# Sheet1.net
KiCad netlist of a schematic drawn in Altium Designer
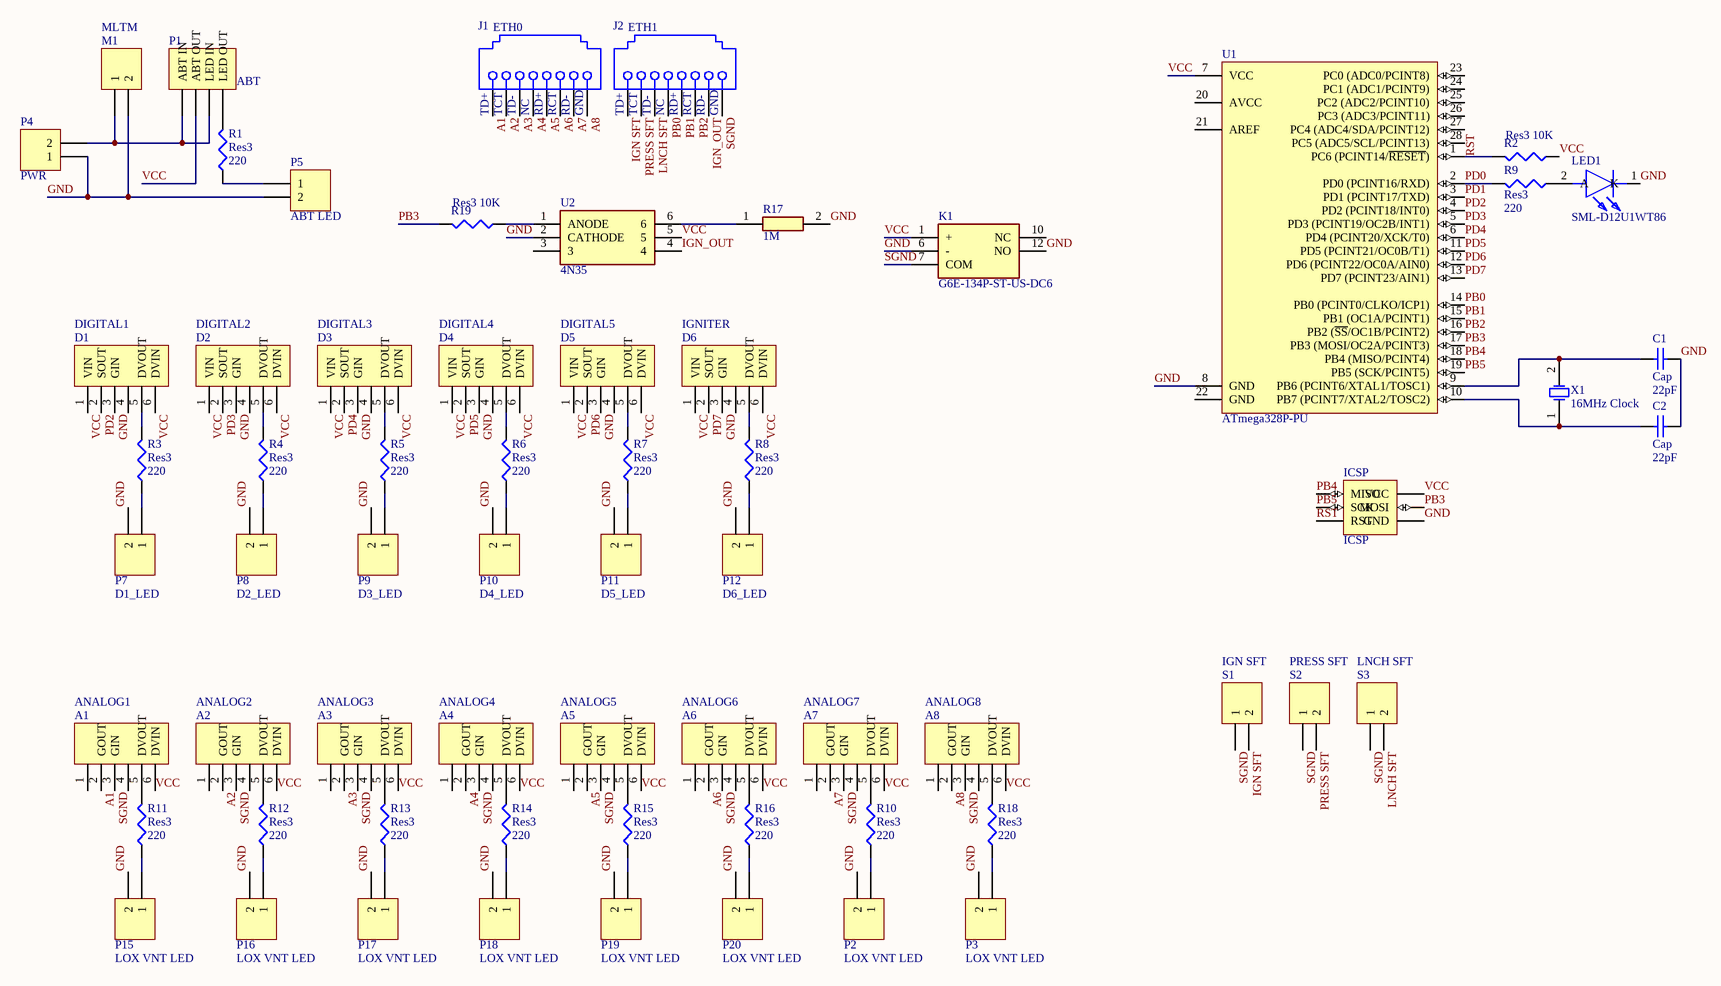
[diagram p0: Sheet1.SchDoc]

(export (version "E")
  (design (tool "Eeschema 10.0.6"))
  (components
    (comp (ref "A1")
      (value "ANALOG1")
      (footprint "HDR1X6")
      (description "Header, 6-Pin")
      (fields (field (name "PUBLISHER") "Altium Limited"))
      (libsource (lib "Miscellaneous Connectors") (part "Header 6"))
    )
    (comp (ref "A2")
      (value "ANALOG2")
      (footprint "HDR1X6")
      (description "Header, 6-Pin")
      (fields (field (name "PUBLISHER") "Altium Limited"))
      (libsource (lib "Miscellaneous Connectors") (part "Header 6"))
    )
    (comp (ref "A3")
      (value "ANALOG3")
      (footprint "HDR1X6")
      (description "Header, 6-Pin")
      (fields (field (name "PUBLISHER") "Altium Limited"))
      (libsource (lib "Miscellaneous Connectors") (part "Header 6"))
    )
    (comp (ref "A4")
      (value "ANALOG4")
      (footprint "HDR1X6")
      (description "Header, 6-Pin")
      (fields (field (name "PUBLISHER") "Altium Limited"))
      (libsource (lib "Miscellaneous Connectors") (part "Header 6"))
    )
    (comp (ref "A5")
      (value "ANALOG5")
      (footprint "HDR1X6")
      (description "Header, 6-Pin")
      (fields (field (name "PUBLISHER") "Altium Limited"))
      (libsource (lib "Miscellaneous Connectors") (part "Header 6"))
    )
    (comp (ref "A6")
      (value "ANALOG6")
      (footprint "HDR1X6")
      (description "Header, 6-Pin")
      (fields (field (name "PUBLISHER") "Altium Limited"))
      (libsource (lib "Miscellaneous Connectors") (part "Header 6"))
    )
    (comp (ref "A7")
      (value "ANALOG7")
      (footprint "HDR1X6")
      (description "Header, 6-Pin")
      (fields (field (name "PUBLISHER") "Altium Limited"))
      (libsource (lib "Miscellaneous Connectors") (part "Header 6"))
    )
    (comp (ref "A8")
      (value "ANALOG8")
      (footprint "HDR1X6")
      (description "Header, 6-Pin")
      (fields (field (name "PUBLISHER") "Altium Limited"))
      (libsource (lib "Miscellaneous Connectors") (part "Header 6"))
    )
    (comp (ref "C1")
      (value "Cap")
      (footprint "RAD-0.3")
      (description "Capacitor")
      (fields (field (name "ALTIUM_VALUE") "22pF") (field (name "PUBLISHER") "Altium Limited"))
      (libsource (lib "Miscellaneous Devices") (part "Cap"))
    )
    (comp (ref "C2")
      (value "Cap")
      (footprint "RAD-0.3")
      (description "Capacitor")
      (fields (field (name "ALTIUM_VALUE") "22pF") (field (name "PUBLISHER") "Altium Limited"))
      (libsource (lib "Miscellaneous Devices") (part "Cap"))
    )
    (comp (ref "D1")
      (value "DIGITAL1")
      (footprint "HDR1X6")
      (description "Header, 6-Pin")
      (fields (field (name "PUBLISHER") "Altium Limited"))
      (libsource (lib "Miscellaneous Connectors") (part "Header 6"))
    )
    (comp (ref "D2")
      (value "DIGITAL2")
      (footprint "HDR1X6")
      (description "Header, 6-Pin")
      (fields (field (name "PUBLISHER") "Altium Limited"))
      (libsource (lib "Miscellaneous Connectors") (part "Header 6"))
    )
    (comp (ref "D3")
      (value "DIGITAL3")
      (footprint "HDR1X6")
      (description "Header, 6-Pin")
      (fields (field (name "PUBLISHER") "Altium Limited"))
      (libsource (lib "Miscellaneous Connectors") (part "Header 6"))
    )
    (comp (ref "D4")
      (value "DIGITAL4")
      (footprint "HDR1X6")
      (description "Header, 6-Pin")
      (fields (field (name "PUBLISHER") "Altium Limited"))
      (libsource (lib "Miscellaneous Connectors") (part "Header 6"))
    )
    (comp (ref "D5")
      (value "DIGITAL5")
      (footprint "HDR1X6")
      (description "Header, 6-Pin")
      (fields (field (name "PUBLISHER") "Altium Limited"))
      (libsource (lib "Miscellaneous Connectors") (part "Header 6"))
    )
    (comp (ref "D6")
      (value "IGNITER")
      (footprint "HDR1X6")
      (description "Header, 6-Pin")
      (fields (field (name "PUBLISHER") "Altium Limited"))
      (libsource (lib "Miscellaneous Connectors") (part "Header 6"))
    )
    (comp (ref "ICSP")
      (value "ICSP")
      (footprint "HDR2X3")
      (description "Header, 3-Pin, Dual row")
      (fields (field (name "PUBLISHER") "Altium Limited"))
      (libsource (lib "Miscellaneous Connectors") (part "Header 3X2"))
    )
    (comp (ref "J1")
      (value "ETH0")
      (footprint "TECO-5555153-1_V")
      (fields (field (name "MANUFACTURER") "TE Connectivity"))
      (libsource (lib "Altium Content Vault") (part "RJ45-8-2SHLD"))
    )
    (comp (ref "J2")
      (value "ETH1")
      (footprint "TECO-5555153-1_V")
      (fields (field (name "MANUFACTURER") "TE Connectivity"))
      (libsource (lib "Altium Content Vault") (part "RJ45-8-2SHLD"))
    )
    (comp (ref "K1")
      (value "G6E-134P-ST-US-DC6")
      (footprint "SamacSys:G6E-134P-US")
      (description "Relay or Contactor")
      (fields (field (name "MOUSER PART NUMBER") "653-G6E134PSTUSDC6"))
      (libsource (lib "*") (part "G6E-134P-ST-US-DC6"))
    )
    (comp (ref "LED1")
      (value "SML-D12U1WT86")
      (footprint "SamacSys:LEDC1608X65N")
      (description "LED")
      (fields
        (field (name "MOUSER PART NUMBER") "755-SML-D12U1WT86")
        (field (name "RS PART NUMBER") "1332870")
      )
      (libsource (lib "*") (part "SML-D12U1WT86"))
    )
    (comp (ref "M1")
      (value "MLTM")
      (footprint "HDR1X2")
      (description "Header, 2-Pin")
      (fields (field (name "PUBLISHER") "Altium Limited"))
      (libsource (lib "Miscellaneous Connectors") (part "Header 2"))
    )
    (comp (ref "P1")
      (value "ABT")
      (footprint "HDR1X4")
      (description "Header, 4-Pin")
      (fields (field (name "PUBLISHER") "Altium Limited"))
      (libsource (lib "Miscellaneous Connectors") (part "Header 4"))
    )
    (comp (ref "P2")
      (value "LOX VNT LED")
      (footprint "HDR1X2")
      (description "Header, 2-Pin")
      (fields (field (name "PUBLISHER") "Altium Limited"))
      (libsource (lib "") (part "Header 2_1"))
    )
    (comp (ref "P3")
      (value "LOX VNT LED")
      (footprint "HDR1X2")
      (description "Header, 2-Pin")
      (fields (field (name "PUBLISHER") "Altium Limited"))
      (libsource (lib "") (part "Header 2_1"))
    )
    (comp (ref "P4")
      (value "PWR")
      (footprint "HDR1X2")
      (description "Header, 2-Pin")
      (fields (field (name "PUBLISHER") "Altium Limited"))
      (libsource (lib "") (part "Header 2_2"))
    )
    (comp (ref "P5")
      (value "ABT LED")
      (footprint "HDR1X2")
      (description "Header, 2-Pin")
      (fields (field (name "PUBLISHER") "Altium Limited"))
      (libsource (lib "") (part "Header 2_3"))
    )
    (comp (ref "P7")
      (value "D1_LED")
      (footprint "HDR1X2")
      (description "Header, 2-Pin")
      (fields (field (name "PUBLISHER") "Altium Limited"))
      (libsource (lib "") (part "Header 2_1"))
    )
    (comp (ref "P8")
      (value "D2_LED")
      (footprint "HDR1X2")
      (description "Header, 2-Pin")
      (fields (field (name "PUBLISHER") "Altium Limited"))
      (libsource (lib "") (part "Header 2_1"))
    )
    (comp (ref "P9")
      (value "D3_LED")
      (footprint "HDR1X2")
      (description "Header, 2-Pin")
      (fields (field (name "PUBLISHER") "Altium Limited"))
      (libsource (lib "") (part "Header 2_1"))
    )
    (comp (ref "P10")
      (value "D4_LED")
      (footprint "HDR1X2")
      (description "Header, 2-Pin")
      (fields (field (name "PUBLISHER") "Altium Limited"))
      (libsource (lib "") (part "Header 2_1"))
    )
    (comp (ref "P11")
      (value "D5_LED")
      (footprint "HDR1X2")
      (description "Header, 2-Pin")
      (fields (field (name "PUBLISHER") "Altium Limited"))
      (libsource (lib "") (part "Header 2_1"))
    )
    (comp (ref "P12")
      (value "D6_LED")
      (footprint "HDR1X2")
      (description "Header, 2-Pin")
      (fields (field (name "PUBLISHER") "Altium Limited"))
      (libsource (lib "") (part "Header 2_1"))
    )
    (comp (ref "P15")
      (value "LOX VNT LED")
      (footprint "HDR1X2")
      (description "Header, 2-Pin")
      (fields (field (name "PUBLISHER") "Altium Limited"))
      (libsource (lib "") (part "Header 2_1"))
    )
    (comp (ref "P16")
      (value "LOX VNT LED")
      (footprint "HDR1X2")
      (description "Header, 2-Pin")
      (fields (field (name "PUBLISHER") "Altium Limited"))
      (libsource (lib "") (part "Header 2_1"))
    )
    (comp (ref "P17")
      (value "LOX VNT LED")
      (footprint "HDR1X2")
      (description "Header, 2-Pin")
      (fields (field (name "PUBLISHER") "Altium Limited"))
      (libsource (lib "") (part "Header 2_1"))
    )
    (comp (ref "P18")
      (value "LOX VNT LED")
      (footprint "HDR1X2")
      (description "Header, 2-Pin")
      (fields (field (name "PUBLISHER") "Altium Limited"))
      (libsource (lib "") (part "Header 2_1"))
    )
    (comp (ref "P19")
      (value "LOX VNT LED")
      (footprint "HDR1X2")
      (description "Header, 2-Pin")
      (fields (field (name "PUBLISHER") "Altium Limited"))
      (libsource (lib "") (part "Header 2_1"))
    )
    (comp (ref "P20")
      (value "LOX VNT LED")
      (footprint "HDR1X2")
      (description "Header, 2-Pin")
      (fields (field (name "PUBLISHER") "Altium Limited"))
      (libsource (lib "") (part "Header 2_1"))
    )
    (comp (ref "R1")
      (value "Res3")
      (footprint "*RESC3146X60N")
      (description "Resistor")
      (fields (field (name "ALTIUM_VALUE") "220") (field (name "PUBLISHER") "Altium Limited"))
      (libsource (lib "Miscellaneous Devices") (part "Res3"))
    )
    (comp (ref "R2")
      (value "Res3")
      (footprint "*RESC3146X60N")
      (description "Resistor")
      (fields (field (name "ALTIUM_VALUE") "10K") (field (name "PUBLISHER") "Altium Limited"))
      (libsource (lib "Miscellaneous Devices") (part "Res3"))
    )
    (comp (ref "R3")
      (value "Res3")
      (footprint "*RESC3146X60N")
      (description "Resistor")
      (fields (field (name "ALTIUM_VALUE") "220") (field (name "PUBLISHER") "Altium Limited"))
      (libsource (lib "Miscellaneous Devices") (part "Res3"))
    )
    (comp (ref "R4")
      (value "Res3")
      (footprint "*RESC3146X60N")
      (description "Resistor")
      (fields (field (name "ALTIUM_VALUE") "220") (field (name "PUBLISHER") "Altium Limited"))
      (libsource (lib "Miscellaneous Devices") (part "Res3"))
    )
    (comp (ref "R5")
      (value "Res3")
      (footprint "*RESC3146X60N")
      (description "Resistor")
      (fields (field (name "ALTIUM_VALUE") "220") (field (name "PUBLISHER") "Altium Limited"))
      (libsource (lib "Miscellaneous Devices") (part "Res3"))
    )
    (comp (ref "R6")
      (value "Res3")
      (footprint "*RESC3146X60N")
      (description "Resistor")
      (fields (field (name "ALTIUM_VALUE") "220") (field (name "PUBLISHER") "Altium Limited"))
      (libsource (lib "Miscellaneous Devices") (part "Res3"))
    )
    (comp (ref "R7")
      (value "Res3")
      (footprint "*RESC3146X60N")
      (description "Resistor")
      (fields (field (name "ALTIUM_VALUE") "220") (field (name "PUBLISHER") "Altium Limited"))
      (libsource (lib "Miscellaneous Devices") (part "Res3"))
    )
    (comp (ref "R8")
      (value "Res3")
      (footprint "*RESC3146X60N")
      (description "Resistor")
      (fields (field (name "ALTIUM_VALUE") "220") (field (name "PUBLISHER") "Altium Limited"))
      (libsource (lib "Miscellaneous Devices") (part "Res3"))
    )
    (comp (ref "R9")
      (value "Res3")
      (footprint "*RESC3146X60N")
      (description "Resistor")
      (fields (field (name "ALTIUM_VALUE") "220") (field (name "PUBLISHER") "Altium Limited"))
      (libsource (lib "Miscellaneous Devices") (part "Res3"))
    )
    (comp (ref "R10")
      (value "Res3")
      (footprint "*RESC3146X60N")
      (description "Resistor")
      (fields (field (name "ALTIUM_VALUE") "220") (field (name "PUBLISHER") "Altium Limited"))
      (libsource (lib "Miscellaneous Devices") (part "Res3"))
    )
    (comp (ref "R11")
      (value "Res3")
      (footprint "*RESC3146X60N")
      (description "Resistor")
      (fields (field (name "ALTIUM_VALUE") "220") (field (name "PUBLISHER") "Altium Limited"))
      (libsource (lib "Miscellaneous Devices") (part "Res3"))
    )
    (comp (ref "R12")
      (value "Res3")
      (footprint "*RESC3146X60N")
      (description "Resistor")
      (fields (field (name "ALTIUM_VALUE") "220") (field (name "PUBLISHER") "Altium Limited"))
      (libsource (lib "Miscellaneous Devices") (part "Res3"))
    )
    (comp (ref "R13")
      (value "Res3")
      (footprint "*RESC3146X60N")
      (description "Resistor")
      (fields (field (name "ALTIUM_VALUE") "220") (field (name "PUBLISHER") "Altium Limited"))
      (libsource (lib "Miscellaneous Devices") (part "Res3"))
    )
    (comp (ref "R14")
      (value "Res3")
      (footprint "*RESC3146X60N")
      (description "Resistor")
      (fields (field (name "ALTIUM_VALUE") "220") (field (name "PUBLISHER") "Altium Limited"))
      (libsource (lib "Miscellaneous Devices") (part "Res3"))
    )
    (comp (ref "R15")
      (value "Res3")
      (footprint "*RESC3146X60N")
      (description "Resistor")
      (fields (field (name "ALTIUM_VALUE") "220") (field (name "PUBLISHER") "Altium Limited"))
      (libsource (lib "Miscellaneous Devices") (part "Res3"))
    )
    (comp (ref "R16")
      (value "Res3")
      (footprint "*RESC3146X60N")
      (description "Resistor")
      (fields (field (name "ALTIUM_VALUE") "220") (field (name "PUBLISHER") "Altium Limited"))
      (libsource (lib "Miscellaneous Devices") (part "Res3"))
    )
    (comp (ref "R17")
      (value "1M")
      (footprint "SamacSys:RESAD1550W60L630D230")
      (description "Resistor")
      (fields
        (field (name "MANUFACTURER_PART_NUMBER") "YR1B1M0CC")
        (field (name "MOUSER PART NUMBER") "279-YR1B1M0CC")
      )
      (libsource (lib "*") (part "YR1B1M0CC"))
    )
    (comp (ref "R18")
      (value "Res3")
      (footprint "*RESC3146X60N")
      (description "Resistor")
      (fields (field (name "ALTIUM_VALUE") "220") (field (name "PUBLISHER") "Altium Limited"))
      (libsource (lib "Miscellaneous Devices") (part "Res3"))
    )
    (comp (ref "R19")
      (value "Res3")
      (footprint "*RESC3146X60N")
      (description "Resistor")
      (fields (field (name "ALTIUM_VALUE") "10K") (field (name "PUBLISHER") "Altium Limited"))
      (libsource (lib "Miscellaneous Devices") (part "Res3"))
    )
    (comp (ref "S1")
      (value "IGN SFT")
      (footprint "HDR1X2")
      (description "Header, 2-Pin")
      (fields (field (name "PUBLISHER") "Altium Limited"))
      (libsource (lib "Miscellaneous Connectors") (part "Header 2"))
    )
    (comp (ref "S2")
      (value "PRESS SFT")
      (footprint "HDR1X2")
      (description "Header, 2-Pin")
      (fields (field (name "PUBLISHER") "Altium Limited"))
      (libsource (lib "Miscellaneous Connectors") (part "Header 2"))
    )
    (comp (ref "S3")
      (value "LNCH SFT")
      (footprint "HDR1X2")
      (description "Header, 2-Pin")
      (fields (field (name "PUBLISHER") "Altium Limited"))
      (libsource (lib "Miscellaneous Connectors") (part "Header 2"))
    )
    (comp (ref "U1")
      (value "ATmega328P-PU")
      (footprint "28P3")
      (libsource (lib "Altium Content Vault") (part "MC-8B-ATM48-IL28"))
    )
    (comp (ref "U2")
      (value "4N35")
      (footprint "SamacSys:DIP762W50P254L712H450Q6N")
      (description "Transistor")
      (fields (field (name "RS PART NUMBER") "1712954"))
      (libsource (lib "*") (part "4N35"))
    )
    (comp (ref "X1")
      (value "16MHz Clock")
      (footprint "CFM-HCM49-2_V")
      (description "At-Cut Crystal Unit, 3.5 to 30 MHz, -40 to 85 degC, 2-Pin 11.4Ã—4.7Ã—4.3 mm SMD, RoHS, Reel")
      (fields
        (field (name "MANUFACTURER") "Citizen Finetech Miyota")
        (field (name "PARTNUMBER") "HCM49-8.000MABJ-UT")
      )
      (libsource (lib "Altium Content Vault") (part "CFM-HCM49-2"))
    )
  )
  (nets
    (net (code "1") (name "/A1") (class "Default")
      (node (ref "A1") (pin "2") (pinfunction "GOUT_2") (pintype "passive"))
      (node (ref "J1") (pin "1") (pinfunction "1_1") (pintype "passive"))
    )
    (net (code "2") (name "/A2") (class "Default")
      (node (ref "A2") (pin "2") (pinfunction "GOUT_2") (pintype "passive"))
      (node (ref "J1") (pin "2") (pinfunction "2_2") (pintype "passive"))
    )
    (net (code "3") (name "/A3") (class "Default")
      (node (ref "A3") (pin "2") (pinfunction "GOUT_2") (pintype "passive"))
      (node (ref "J1") (pin "3") (pinfunction "3_3") (pintype "passive"))
    )
    (net (code "4") (name "/A4") (class "Default")
      (node (ref "A4") (pin "2") (pinfunction "GOUT_2") (pintype "passive"))
      (node (ref "J1") (pin "4") (pinfunction "4_4") (pintype "passive"))
    )
    (net (code "5") (name "/A5") (class "Default")
      (node (ref "A5") (pin "2") (pinfunction "GOUT_2") (pintype "passive"))
      (node (ref "J1") (pin "5") (pinfunction "5_5") (pintype "passive"))
    )
    (net (code "6") (name "/A6") (class "Default")
      (node (ref "A6") (pin "2") (pinfunction "GOUT_2") (pintype "passive"))
      (node (ref "J1") (pin "6") (pinfunction "6_6") (pintype "passive"))
    )
    (net (code "7") (name "/A7") (class "Default")
      (node (ref "A7") (pin "2") (pinfunction "GOUT_2") (pintype "passive"))
      (node (ref "J1") (pin "7") (pinfunction "7_7") (pintype "passive"))
    )
    (net (code "8") (name "/A8") (class "Default")
      (node (ref "A8") (pin "2") (pinfunction "GOUT_2") (pintype "passive"))
      (node (ref "J1") (pin "8") (pinfunction "8_8") (pintype "passive"))
    )
    (net (code "9") (name "/GND") (class "Default")
      (node (ref "C1") (pin "2") (pinfunction "2_2") (pintype "passive"))
      (node (ref "C2") (pin "2") (pinfunction "2_2") (pintype "passive"))
      (node (ref "D1") (pin "3") (pinfunction "GIN_3") (pintype "passive"))
      (node (ref "D2") (pin "3") (pinfunction "GIN_3") (pintype "passive"))
      (node (ref "D3") (pin "3") (pinfunction "GIN_3") (pintype "passive"))
      (node (ref "D4") (pin "3") (pinfunction "GIN_3") (pintype "passive"))
      (node (ref "D5") (pin "3") (pinfunction "GIN_3") (pintype "passive"))
      (node (ref "D6") (pin "3") (pinfunction "GIN_3") (pintype "passive"))
      (node (ref "ICSP") (pin "6") (pinfunction "GND_6") (pintype "passive"))
      (node (ref "K1") (pin "12") (pinfunction "NO_12") (pintype "passive"))
      (node (ref "K1") (pin "6") (pinfunction "-_6") (pintype "passive"))
      (node (ref "LED1") (pin "1") (pinfunction "K_1") (pintype "passive"))
      (node (ref "M1") (pin "2") (pinfunction "2_2") (pintype "passive"))
      (node (ref "P10") (pin "2") (pinfunction "2_2") (pintype "passive"))
      (node (ref "P11") (pin "2") (pinfunction "2_2") (pintype "passive"))
      (node (ref "P12") (pin "2") (pinfunction "2_2") (pintype "passive"))
      (node (ref "P15") (pin "2") (pinfunction "2_2") (pintype "passive"))
      (node (ref "P16") (pin "2") (pinfunction "2_2") (pintype "passive"))
      (node (ref "P17") (pin "2") (pinfunction "2_2") (pintype "passive"))
      (node (ref "P18") (pin "2") (pinfunction "2_2") (pintype "passive"))
      (node (ref "P19") (pin "2") (pinfunction "2_2") (pintype "passive"))
      (node (ref "P2") (pin "2") (pinfunction "2_2") (pintype "passive"))
      (node (ref "P20") (pin "2") (pinfunction "2_2") (pintype "passive"))
      (node (ref "P3") (pin "2") (pinfunction "2_2") (pintype "passive"))
      (node (ref "P4") (pin "1") (pinfunction "1_1") (pintype "passive"))
      (node (ref "P5") (pin "2") (pinfunction "2_2") (pintype "passive"))
      (node (ref "P7") (pin "2") (pinfunction "2_2") (pintype "passive"))
      (node (ref "P8") (pin "2") (pinfunction "2_2") (pintype "passive"))
      (node (ref "P9") (pin "2") (pinfunction "2_2") (pintype "passive"))
      (node (ref "R17") (pin "2") (pinfunction "2_2") (pintype "passive"))
      (node (ref "U1") (pin "8") (pinfunction "GND_8") (pintype "power_in"))
      (node (ref "U2") (pin "2") (pinfunction "CATHODE_2") (pintype "passive"))
    )
    (net (code "10") (name "/IGN SFT") (class "Default")
      (node (ref "J2") (pin "1") (pinfunction "1_1") (pintype "passive"))
      (node (ref "S1") (pin "2") (pinfunction "2_2") (pintype "passive"))
    )
    (net (code "11") (name "/IGN_OUT") (class "Default")
      (node (ref "J2") (pin "7") (pinfunction "7_7") (pintype "passive"))
      (node (ref "U2") (pin "4") (pinfunction "4_4") (pintype "passive"))
    )
    (net (code "12") (name "/LNCH SFT") (class "Default")
      (node (ref "J2") (pin "3") (pinfunction "3_3") (pintype "passive"))
      (node (ref "S3") (pin "2") (pinfunction "2_2") (pintype "passive"))
    )
    (net (code "13") (name "/PB0") (class "Default")
      (node (ref "J2") (pin "4") (pinfunction "4_4") (pintype "passive"))
      (node (ref "U1") (pin "14") (pinfunction "PB0_(PCINT0/CLKO/ICP1)_14") (pintype "bidirectional"))
    )
    (net (code "14") (name "/PB1") (class "Default")
      (node (ref "J2") (pin "5") (pinfunction "5_5") (pintype "passive"))
      (node (ref "U1") (pin "15") (pinfunction "PB1_(OC1A/PCINT1)_15") (pintype "bidirectional"))
    )
    (net (code "15") (name "/PB2") (class "Default")
      (node (ref "J2") (pin "6") (pinfunction "6_6") (pintype "passive"))
      (node (ref "U1") (pin "16") (pinfunction "PB2_(~{SS}/OC1B/PCINT2)_16") (pintype "bidirectional"))
    )
    (net (code "16") (name "/PB3") (class "Default")
      (node (ref "ICSP") (pin "4") (pinfunction "MOSI_4") (pintype "bidirectional"))
      (node (ref "R19") (pin "2") (pinfunction "2_2") (pintype "passive"))
      (node (ref "U1") (pin "17") (pinfunction "PB3_(MOSI/OC2A/PCINT3)_17") (pintype "bidirectional"))
    )
    (net (code "17") (name "/PB4") (class "Default")
      (node (ref "ICSP") (pin "1") (pinfunction "MISO_1") (pintype "bidirectional"))
      (node (ref "U1") (pin "18") (pinfunction "PB4_(MISO/PCINT4)_18") (pintype "bidirectional"))
    )
    (net (code "18") (name "/PB5") (class "Default")
      (node (ref "ICSP") (pin "3") (pinfunction "SCK_3") (pintype "bidirectional"))
      (node (ref "U1") (pin "19") (pinfunction "PB5_(SCK/PCINT5)_19") (pintype "bidirectional"))
    )
    (net (code "19") (name "/PD0") (class "Default")
      (node (ref "R9") (pin "2") (pinfunction "2_2") (pintype "passive"))
      (node (ref "U1") (pin "2") (pinfunction "PD0_(PCINT16/RXD)_2") (pintype "bidirectional"))
    )
    (net (code "20") (name "/PD1") (class "Default")
      (node (ref "U1") (pin "3") (pinfunction "PD1_(PCINT17/TXD)_3") (pintype "bidirectional"))
    )
    (net (code "21") (name "/PD2") (class "Default")
      (node (ref "D1") (pin "2") (pinfunction "GOUT_2") (pintype "passive"))
      (node (ref "U1") (pin "4") (pinfunction "PD2_(PCINT18/INT0)_4") (pintype "bidirectional"))
    )
    (net (code "22") (name "/PD3") (class "Default")
      (node (ref "D2") (pin "2") (pinfunction "GOUT_2") (pintype "passive"))
      (node (ref "U1") (pin "5") (pinfunction "PD3_(PCINT19/OC2B/INT1)_5") (pintype "bidirectional"))
    )
    (net (code "23") (name "/PD4") (class "Default")
      (node (ref "D3") (pin "2") (pinfunction "GOUT_2") (pintype "passive"))
      (node (ref "U1") (pin "6") (pinfunction "PD4_(PCINT20/XCK/T0)_6") (pintype "bidirectional"))
    )
    (net (code "24") (name "/PD5") (class "Default")
      (node (ref "D4") (pin "2") (pinfunction "GOUT_2") (pintype "passive"))
      (node (ref "U1") (pin "11") (pinfunction "PD5_(PCINT21/OC0B/T1)_11") (pintype "bidirectional"))
    )
    (net (code "25") (name "/PD6") (class "Default")
      (node (ref "D5") (pin "2") (pinfunction "GOUT_2") (pintype "passive"))
      (node (ref "U1") (pin "12") (pinfunction "PD6_(PCINT22/OC0A/AIN0)_12") (pintype "bidirectional"))
    )
    (net (code "26") (name "/PD7") (class "Default")
      (node (ref "D6") (pin "2") (pinfunction "GOUT_2") (pintype "passive"))
      (node (ref "U1") (pin "13") (pinfunction "PD7_(PCINT23/AIN1)_13") (pintype "bidirectional"))
    )
    (net (code "27") (name "/PRESS SFT") (class "Default")
      (node (ref "J2") (pin "2") (pinfunction "2_2") (pintype "passive"))
      (node (ref "S2") (pin "2") (pinfunction "2_2") (pintype "passive"))
    )
    (net (code "28") (name "/RST") (class "Default")
      (node (ref "ICSP") (pin "5") (pinfunction "RST_5") (pintype "passive"))
      (node (ref "R2") (pin "2") (pinfunction "2_2") (pintype "passive"))
      (node (ref "U1") (pin "1") (pinfunction "PC6_(PCINT14/~{RESET})_1") (pintype "bidirectional"))
    )
    (net (code "29") (name "/SGND") (class "Default")
      (node (ref "A1") (pin "3") (pinfunction "GIN_3") (pintype "passive"))
      (node (ref "A2") (pin "3") (pinfunction "GIN_3") (pintype "passive"))
      (node (ref "A3") (pin "3") (pinfunction "GIN_3") (pintype "passive"))
      (node (ref "A4") (pin "3") (pinfunction "GIN_3") (pintype "passive"))
      (node (ref "A5") (pin "3") (pinfunction "GIN_3") (pintype "passive"))
      (node (ref "A6") (pin "3") (pinfunction "GIN_3") (pintype "passive"))
      (node (ref "A7") (pin "3") (pinfunction "GIN_3") (pintype "passive"))
      (node (ref "A8") (pin "3") (pinfunction "GIN_3") (pintype "passive"))
      (node (ref "J2") (pin "8") (pinfunction "8_8") (pintype "passive"))
      (node (ref "K1") (pin "7") (pinfunction "COM_7") (pintype "passive"))
      (node (ref "S1") (pin "1") (pinfunction "1_1") (pintype "passive"))
      (node (ref "S2") (pin "1") (pinfunction "1_1") (pintype "passive"))
      (node (ref "S3") (pin "1") (pinfunction "1_1") (pintype "passive"))
    )
    (net (code "30") (name "/VCC") (class "Default")
      (node (ref "A1") (pin "6") (pinfunction "DVIN_6") (pintype "passive"))
      (node (ref "A2") (pin "6") (pinfunction "DVIN_6") (pintype "passive"))
      (node (ref "A3") (pin "6") (pinfunction "DVIN_6") (pintype "passive"))
      (node (ref "A4") (pin "6") (pinfunction "DVIN_6") (pintype "passive"))
      (node (ref "A5") (pin "6") (pinfunction "DVIN_6") (pintype "passive"))
      (node (ref "A6") (pin "6") (pinfunction "DVIN_6") (pintype "passive"))
      (node (ref "A7") (pin "6") (pinfunction "DVIN_6") (pintype "passive"))
      (node (ref "A8") (pin "6") (pinfunction "DVIN_6") (pintype "passive"))
      (node (ref "D1") (pin "1") (pintype "passive"))
      (node (ref "D1") (pin "6") (pinfunction "DVIN_6") (pintype "passive"))
      (node (ref "D2") (pin "1") (pintype "passive"))
      (node (ref "D2") (pin "6") (pinfunction "DVIN_6") (pintype "passive"))
      (node (ref "D3") (pin "1") (pintype "passive"))
      (node (ref "D3") (pin "6") (pinfunction "DVIN_6") (pintype "passive"))
      (node (ref "D4") (pin "1") (pintype "passive"))
      (node (ref "D4") (pin "6") (pinfunction "DVIN_6") (pintype "passive"))
      (node (ref "D5") (pin "1") (pintype "passive"))
      (node (ref "D5") (pin "6") (pinfunction "DVIN_6") (pintype "passive"))
      (node (ref "D6") (pin "1") (pintype "passive"))
      (node (ref "D6") (pin "6") (pinfunction "DVIN_6") (pintype "passive"))
      (node (ref "ICSP") (pin "2") (pinfunction "VCC_2") (pintype "power_in"))
      (node (ref "K1") (pin "1") (pinfunction "+_1") (pintype "passive"))
      (node (ref "P1") (pin "2") (pinfunction "ABT_OUT_2") (pintype "passive"))
      (node (ref "R2") (pin "1") (pinfunction "1_1") (pintype "passive"))
      (node (ref "U1") (pin "7") (pinfunction "VCC_7") (pintype "power_in"))
      (node (ref "U2") (pin "5") (pinfunction "5_5") (pintype "passive"))
    )
    (net (code "31") (name "Net-(A1-DVOUT)") (class "Default")
      (node (ref "A1") (pin "5") (pinfunction "DVOUT_5") (pintype "passive"))
      (node (ref "R11") (pin "2") (pinfunction "2_2") (pintype "passive"))
    )
    (net (code "32") (name "Net-(A2-DVOUT)") (class "Default")
      (node (ref "A2") (pin "5") (pinfunction "DVOUT_5") (pintype "passive"))
      (node (ref "R12") (pin "2") (pinfunction "2_2") (pintype "passive"))
    )
    (net (code "33") (name "Net-(A3-DVOUT)") (class "Default")
      (node (ref "A3") (pin "5") (pinfunction "DVOUT_5") (pintype "passive"))
      (node (ref "R13") (pin "2") (pinfunction "2_2") (pintype "passive"))
    )
    (net (code "34") (name "Net-(A4-DVOUT)") (class "Default")
      (node (ref "A4") (pin "5") (pinfunction "DVOUT_5") (pintype "passive"))
      (node (ref "R14") (pin "2") (pinfunction "2_2") (pintype "passive"))
    )
    (net (code "35") (name "Net-(A5-DVOUT)") (class "Default")
      (node (ref "A5") (pin "5") (pinfunction "DVOUT_5") (pintype "passive"))
      (node (ref "R15") (pin "2") (pinfunction "2_2") (pintype "passive"))
    )
    (net (code "36") (name "Net-(A6-DVOUT)") (class "Default")
      (node (ref "A6") (pin "5") (pinfunction "DVOUT_5") (pintype "passive"))
      (node (ref "R16") (pin "2") (pinfunction "2_2") (pintype "passive"))
    )
    (net (code "37") (name "Net-(A7-DVOUT)") (class "Default")
      (node (ref "A7") (pin "5") (pinfunction "DVOUT_5") (pintype "passive"))
      (node (ref "R10") (pin "2") (pinfunction "2_2") (pintype "passive"))
    )
    (net (code "38") (name "Net-(A8-DVOUT)") (class "Default")
      (node (ref "A8") (pin "5") (pinfunction "DVOUT_5") (pintype "passive"))
      (node (ref "R18") (pin "2") (pinfunction "2_2") (pintype "passive"))
    )
    (net (code "39") (name "Net-(D1-DVOUT)") (class "Default")
      (node (ref "D1") (pin "5") (pinfunction "DVOUT_5") (pintype "passive"))
      (node (ref "R3") (pin "2") (pinfunction "2_2") (pintype "passive"))
    )
    (net (code "40") (name "Net-(D2-DVOUT)") (class "Default")
      (node (ref "D2") (pin "5") (pinfunction "DVOUT_5") (pintype "passive"))
      (node (ref "R4") (pin "2") (pinfunction "2_2") (pintype "passive"))
    )
    (net (code "41") (name "Net-(D3-DVOUT)") (class "Default")
      (node (ref "D3") (pin "5") (pinfunction "DVOUT_5") (pintype "passive"))
      (node (ref "R5") (pin "2") (pinfunction "2_2") (pintype "passive"))
    )
    (net (code "42") (name "Net-(D4-DVOUT)") (class "Default")
      (node (ref "D4") (pin "5") (pinfunction "DVOUT_5") (pintype "passive"))
      (node (ref "R6") (pin "2") (pinfunction "2_2") (pintype "passive"))
    )
    (net (code "43") (name "Net-(D5-DVOUT)") (class "Default")
      (node (ref "D5") (pin "5") (pinfunction "DVOUT_5") (pintype "passive"))
      (node (ref "R7") (pin "2") (pinfunction "2_2") (pintype "passive"))
    )
    (net (code "44") (name "Net-(D6-DVOUT)") (class "Default")
      (node (ref "D6") (pin "5") (pinfunction "DVOUT_5") (pintype "passive"))
      (node (ref "R8") (pin "2") (pinfunction "2_2") (pintype "passive"))
    )
    (net (code "45") (name "Net-(LED1-A)") (class "Default")
      (node (ref "LED1") (pin "2") (pinfunction "A_2") (pintype "passive"))
      (node (ref "R9") (pin "1") (pinfunction "1_1") (pintype "passive"))
    )
    (net (code "46") (name "Net-(P1-ABT_IN)") (class "Default")
      (node (ref "M1") (pin "1") (pinfunction "1_1") (pintype "passive"))
      (node (ref "P1") (pin "1") (pinfunction "ABT_IN_1") (pintype "passive"))
      (node (ref "P1") (pin "3") (pinfunction "LED_IN_3") (pintype "passive"))
      (node (ref "P4") (pin "2") (pinfunction "2_2") (pintype "passive"))
    )
    (net (code "47") (name "Net-(P1-LED_OUT)") (class "Default")
      (node (ref "P1") (pin "4") (pinfunction "LED_OUT_4") (pintype "passive"))
      (node (ref "R1") (pin "2") (pinfunction "2_2") (pintype "passive"))
    )
    (net (code "48") (name "Net-(P2-Pad1)") (class "Default")
      (node (ref "P2") (pin "1") (pinfunction "1_1") (pintype "passive"))
      (node (ref "R10") (pin "1") (pinfunction "1_1") (pintype "passive"))
    )
    (net (code "49") (name "Net-(P3-Pad1)") (class "Default")
      (node (ref "P3") (pin "1") (pinfunction "1_1") (pintype "passive"))
      (node (ref "R18") (pin "1") (pinfunction "1_1") (pintype "passive"))
    )
    (net (code "50") (name "Net-(P5-Pad1)") (class "Default")
      (node (ref "P5") (pin "1") (pinfunction "1_1") (pintype "passive"))
      (node (ref "R1") (pin "1") (pinfunction "1_1") (pintype "passive"))
    )
    (net (code "51") (name "Net-(P7-Pad1)") (class "Default")
      (node (ref "P7") (pin "1") (pinfunction "1_1") (pintype "passive"))
      (node (ref "R3") (pin "1") (pinfunction "1_1") (pintype "passive"))
    )
    (net (code "52") (name "Net-(P8-Pad1)") (class "Default")
      (node (ref "P8") (pin "1") (pinfunction "1_1") (pintype "passive"))
      (node (ref "R4") (pin "1") (pinfunction "1_1") (pintype "passive"))
    )
    (net (code "53") (name "Net-(P9-Pad1)") (class "Default")
      (node (ref "P9") (pin "1") (pinfunction "1_1") (pintype "passive"))
      (node (ref "R5") (pin "1") (pinfunction "1_1") (pintype "passive"))
    )
    (net (code "54") (name "Net-(P10-Pad1)") (class "Default")
      (node (ref "P10") (pin "1") (pinfunction "1_1") (pintype "passive"))
      (node (ref "R6") (pin "1") (pinfunction "1_1") (pintype "passive"))
    )
    (net (code "55") (name "Net-(P11-Pad1)") (class "Default")
      (node (ref "P11") (pin "1") (pinfunction "1_1") (pintype "passive"))
      (node (ref "R7") (pin "1") (pinfunction "1_1") (pintype "passive"))
    )
    (net (code "56") (name "Net-(P12-Pad1)") (class "Default")
      (node (ref "P12") (pin "1") (pinfunction "1_1") (pintype "passive"))
      (node (ref "R8") (pin "1") (pinfunction "1_1") (pintype "passive"))
    )
    (net (code "57") (name "Net-(P15-Pad1)") (class "Default")
      (node (ref "P15") (pin "1") (pinfunction "1_1") (pintype "passive"))
      (node (ref "R11") (pin "1") (pinfunction "1_1") (pintype "passive"))
    )
    (net (code "58") (name "Net-(P16-Pad1)") (class "Default")
      (node (ref "P16") (pin "1") (pinfunction "1_1") (pintype "passive"))
      (node (ref "R12") (pin "1") (pinfunction "1_1") (pintype "passive"))
    )
    (net (code "59") (name "Net-(P17-Pad1)") (class "Default")
      (node (ref "P17") (pin "1") (pinfunction "1_1") (pintype "passive"))
      (node (ref "R13") (pin "1") (pinfunction "1_1") (pintype "passive"))
    )
    (net (code "60") (name "Net-(P18-Pad1)") (class "Default")
      (node (ref "P18") (pin "1") (pinfunction "1_1") (pintype "passive"))
      (node (ref "R14") (pin "1") (pinfunction "1_1") (pintype "passive"))
    )
    (net (code "61") (name "Net-(P19-Pad1)") (class "Default")
      (node (ref "P19") (pin "1") (pinfunction "1_1") (pintype "passive"))
      (node (ref "R15") (pin "1") (pinfunction "1_1") (pintype "passive"))
    )
    (net (code "62") (name "Net-(P20-Pad1)") (class "Default")
      (node (ref "P20") (pin "1") (pinfunction "1_1") (pintype "passive"))
      (node (ref "R16") (pin "1") (pinfunction "1_1") (pintype "passive"))
    )
    (net (code "63") (name "Net-(R17-Pad1)") (class "Default")
      (node (ref "R17") (pin "1") (pinfunction "1_1") (pintype "passive"))
      (node (ref "U2") (pin "6") (pinfunction "6_6") (pintype "passive"))
    )
    (net (code "64") (name "Net-(U1-PB6_(PCINT6{slash}XTAL1{slash}TOSC1))") (class "Default")
      (node (ref "C1") (pin "1") (pinfunction "1_1") (pintype "passive"))
      (node (ref "U1") (pin "9") (pinfunction "PB6_(PCINT6/XTAL1/TOSC1)_9") (pintype "bidirectional"))
      (node (ref "X1") (pin "2") (pinfunction "X2_2") (pintype "passive"))
    )
    (net (code "65") (name "Net-(U1-PB7_(PCINT7{slash}XTAL2{slash}TOSC2))") (class "Default")
      (node (ref "C2") (pin "1") (pinfunction "1_1") (pintype "passive"))
      (node (ref "U1") (pin "10") (pinfunction "PB7_(PCINT7/XTAL2/TOSC2)_10") (pintype "bidirectional"))
      (node (ref "X1") (pin "1") (pinfunction "X1_1") (pintype "passive"))
    )
    (net (code "66") (name "Net-(U2-ANODE)") (class "Default")
      (node (ref "R19") (pin "1") (pinfunction "1_1") (pintype "passive"))
      (node (ref "U2") (pin "1") (pinfunction "ANODE_1") (pintype "passive"))
    )
    (net (code "67") (name "unconnected-(A1-Pad1)") (class "Default")
      (node (ref "A1") (pin "1") (pintype "passive"))
    )
    (net (code "68") (name "unconnected-(A1-Pad4)") (class "Default")
      (node (ref "A1") (pin "4") (pintype "passive"))
    )
    (net (code "69") (name "unconnected-(A2-Pad1)") (class "Default")
      (node (ref "A2") (pin "1") (pintype "passive"))
    )
    (net (code "70") (name "unconnected-(A2-Pad4)") (class "Default")
      (node (ref "A2") (pin "4") (pintype "passive"))
    )
    (net (code "71") (name "unconnected-(A3-Pad1)") (class "Default")
      (node (ref "A3") (pin "1") (pintype "passive"))
    )
    (net (code "72") (name "unconnected-(A3-Pad4)") (class "Default")
      (node (ref "A3") (pin "4") (pintype "passive"))
    )
    (net (code "73") (name "unconnected-(A4-Pad1)") (class "Default")
      (node (ref "A4") (pin "1") (pintype "passive"))
    )
    (net (code "74") (name "unconnected-(A4-Pad4)") (class "Default")
      (node (ref "A4") (pin "4") (pintype "passive"))
    )
    (net (code "75") (name "unconnected-(A5-Pad1)") (class "Default")
      (node (ref "A5") (pin "1") (pintype "passive"))
    )
    (net (code "76") (name "unconnected-(A5-Pad4)") (class "Default")
      (node (ref "A5") (pin "4") (pintype "passive"))
    )
    (net (code "77") (name "unconnected-(A6-Pad1)") (class "Default")
      (node (ref "A6") (pin "1") (pintype "passive"))
    )
    (net (code "78") (name "unconnected-(A6-Pad4)") (class "Default")
      (node (ref "A6") (pin "4") (pintype "passive"))
    )
    (net (code "79") (name "unconnected-(A7-Pad1)") (class "Default")
      (node (ref "A7") (pin "1") (pintype "passive"))
    )
    (net (code "80") (name "unconnected-(A7-Pad4)") (class "Default")
      (node (ref "A7") (pin "4") (pintype "passive"))
    )
    (net (code "81") (name "unconnected-(A8-Pad1)") (class "Default")
      (node (ref "A8") (pin "1") (pintype "passive"))
    )
    (net (code "82") (name "unconnected-(A8-Pad4)") (class "Default")
      (node (ref "A8") (pin "4") (pintype "passive"))
    )
    (net (code "83") (name "unconnected-(D1-Pad4)") (class "Default")
      (node (ref "D1") (pin "4") (pintype "passive"))
    )
    (net (code "84") (name "unconnected-(D2-Pad4)") (class "Default")
      (node (ref "D2") (pin "4") (pintype "passive"))
    )
    (net (code "85") (name "unconnected-(D3-Pad4)") (class "Default")
      (node (ref "D3") (pin "4") (pintype "passive"))
    )
    (net (code "86") (name "unconnected-(D4-Pad4)") (class "Default")
      (node (ref "D4") (pin "4") (pintype "passive"))
    )
    (net (code "87") (name "unconnected-(D5-Pad4)") (class "Default")
      (node (ref "D5") (pin "4") (pintype "passive"))
    )
    (net (code "88") (name "unconnected-(D6-Pad4)") (class "Default")
      (node (ref "D6") (pin "4") (pintype "passive"))
    )
    (net (code "89") (name "unconnected-(J1-PadS1)") (class "Default")
      (node (ref "J1") (pin "S1") (pintype "passive"))
    )
    (net (code "90") (name "unconnected-(J1-PadS2)") (class "Default")
      (node (ref "J1") (pin "S2") (pintype "passive"))
    )
    (net (code "91") (name "unconnected-(J2-PadS1)") (class "Default")
      (node (ref "J2") (pin "S1") (pintype "passive"))
    )
    (net (code "92") (name "unconnected-(J2-PadS2)") (class "Default")
      (node (ref "J2") (pin "S2") (pintype "passive"))
    )
    (net (code "93") (name "unconnected-(K1-NC-Pad10)") (class "Default")
      (node (ref "K1") (pin "10") (pinfunction "NC_10") (pintype "passive"))
    )
    (net (code "94") (name "unconnected-(U1-AREF-Pad21)") (class "Default")
      (node (ref "U1") (pin "21") (pinfunction "AREF_21") (pintype "power_in"))
    )
    (net (code "95") (name "unconnected-(U1-AVCC-Pad20)") (class "Default")
      (node (ref "U1") (pin "20") (pinfunction "AVCC_20") (pintype "power_in"))
    )
    (net (code "96") (name "unconnected-(U1-GND-Pad22)") (class "Default")
      (node (ref "U1") (pin "22") (pinfunction "GND_22") (pintype "power_in"))
    )
    (net (code "97") (name "unconnected-(U1-PC0_(ADC0{slash}PCINT8)-Pad23)") (class "Default")
      (node (ref "U1") (pin "23") (pinfunction "PC0_(ADC0/PCINT8)_23") (pintype "bidirectional"))
    )
    (net (code "98") (name "unconnected-(U1-PC1_(ADC1{slash}PCINT9)-Pad24)") (class "Default")
      (node (ref "U1") (pin "24") (pinfunction "PC1_(ADC1/PCINT9)_24") (pintype "bidirectional"))
    )
    (net (code "99") (name "unconnected-(U1-PC2_(ADC2{slash}PCINT10)-Pad25)") (class "Default")
      (node (ref "U1") (pin "25") (pinfunction "PC2_(ADC2/PCINT10)_25") (pintype "bidirectional"))
    )
    (net (code "100") (name "unconnected-(U1-PC3_(ADC3{slash}PCINT11)-Pad26)") (class "Default")
      (node (ref "U1") (pin "26") (pinfunction "PC3_(ADC3/PCINT11)_26") (pintype "bidirectional"))
    )
    (net (code "101") (name "unconnected-(U1-PC4_(ADC4{slash}SDA{slash}PCINT12)-Pad27)") (class "Default")
      (node (ref "U1") (pin "27") (pinfunction "PC4_(ADC4/SDA/PCINT12)_27") (pintype "bidirectional"))
    )
    (net (code "102") (name "unconnected-(U1-PC5_(ADC5{slash}SCL{slash}PCINT13)-Pad28)") (class "Default")
      (node (ref "U1") (pin "28") (pinfunction "PC5_(ADC5/SCL/PCINT13)_28") (pintype "bidirectional"))
    )
    (net (code "103") (name "unconnected-(U2-Pad3)") (class "Default")
      (node (ref "U2") (pin "3") (pinfunction "3_3") (pintype "passive"))
    )
  )
)
